# Sch_Raspi_Hat.net
KiCad netlist of a schematic drawn in Altium Designer
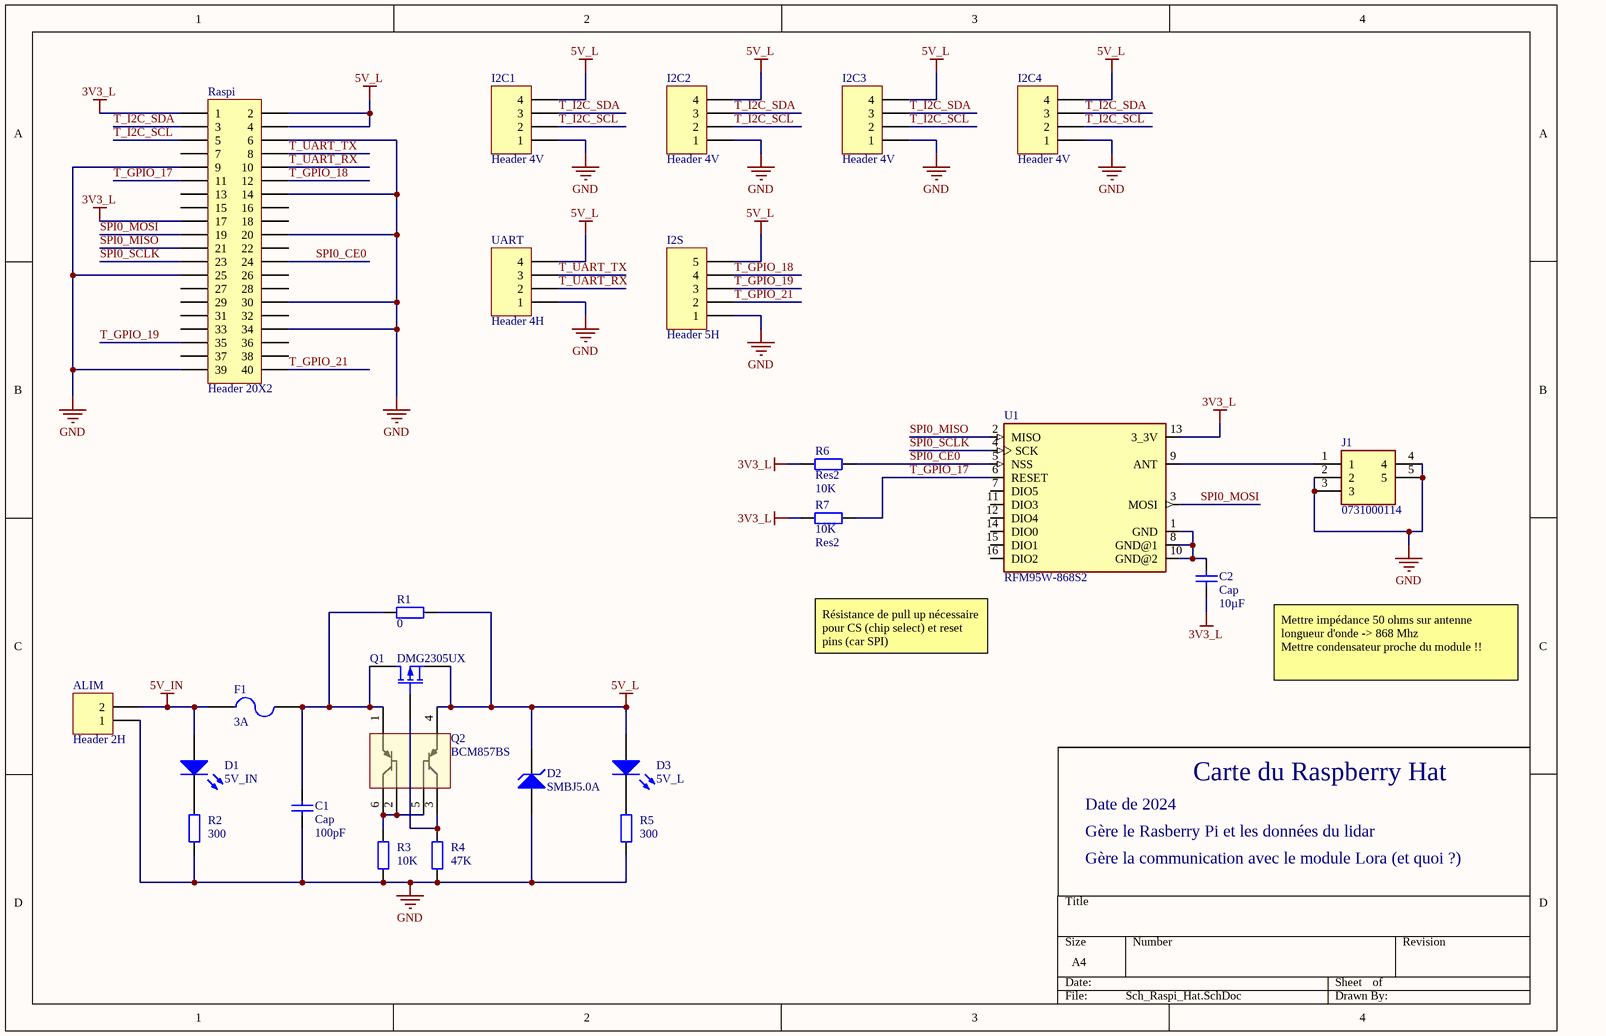
[diagram p0: Sch_Raspi_Hat.SchDoc]

(export (version "E")
  (design (tool "Eeschema 10.0.6"))
  (components
    (comp (ref "ALIM")
      (value "Header 2H")
      (footprint "Molex_MiniFitJr_2x1H")
      (description "Header, 2-Pin, Right Angle")
      (fields (field (name "PUBLISHER") "Altium Limited"))
      (libsource (lib "Miscellaneous Connectors") (part "Header 2H"))
    )
    (comp (ref "C1")
      (value "Cap")
      (footprint "Capacitor 1206")
      (description "Capacitor")
      (fields (field (name "ALTIUM_VALUE") "100pF") (field (name "PUBLISHER") "Altium Limited"))
      (libsource (lib "Miscellaneous Devices") (part "Cap"))
    )
    (comp (ref "C2")
      (value "Cap")
      (footprint "Capacitor 1206")
      (description "Capacitor")
      (fields (field (name "ALTIUM_VALUE") "10µF") (field (name "PUBLISHER") "Altium Limited"))
      (libsource (lib "Miscellaneous Devices") (part "Cap"))
    )
    (comp (ref "D1")
      (value "5V_IN")
      (footprint "KP-3216SEC")
      (description "Typical RED, GREEN, YELLOW, AMBER GaAs LED")
      (fields (field (name "PUBLISHER") "Altium Limited"))
      (libsource (lib "Miscellaneous Devices") (part "LED2"))
    )
    (comp (ref "D2")
      (value "SMBJ5.0A")
      (footprint "SMB")
      (description "Zener Diode")
      (fields (field (name "PUBLISHER") "Altium Limited"))
      (libsource (lib "Miscellaneous Devices") (part "D Zener"))
    )
    (comp (ref "D3")
      (value "5V_L")
      (footprint "KP-3216SEC")
      (description "Typical RED, GREEN, YELLOW, AMBER GaAs LED")
      (fields (field (name "PUBLISHER") "Altium Limited"))
      (libsource (lib "Miscellaneous Devices") (part "LED2"))
    )
    (comp (ref "F1")
      (value "3A")
      (footprint "Resistor 1206")
      (description "Fuse")
      (fields (field (name "PUBLISHER") "Altium Limited"))
      (libsource (lib "Miscellaneous Devices") (part "Fuse 2"))
    )
    (comp (ref "I2C1")
      (value "Header 4V")
      (footprint "B4BXHALFSN")
      (description "Header, 4-Pin, Right Angle")
      (fields (field (name "PUBLISHER") "Altium Limited"))
      (libsource (lib "Miscellaneous Connectors") (part "Header 4H"))
    )
    (comp (ref "I2C2")
      (value "Header 4V")
      (footprint "B4BXHALFSN")
      (description "Header, 4-Pin, Right Angle")
      (fields (field (name "PUBLISHER") "Altium Limited"))
      (libsource (lib "Miscellaneous Connectors") (part "Header 4H"))
    )
    (comp (ref "I2C3")
      (value "Header 4V")
      (footprint "B4BXHALFSN")
      (description "Header, 4-Pin, Right Angle")
      (fields (field (name "PUBLISHER") "Altium Limited"))
      (libsource (lib "Miscellaneous Connectors") (part "Header 4H"))
    )
    (comp (ref "I2C4")
      (value "Header 4V")
      (footprint "B4BXHALFSN")
      (description "Header, 4-Pin, Right Angle")
      (fields (field (name "PUBLISHER") "Altium Limited"))
      (libsource (lib "Miscellaneous Connectors") (part "Header 4H"))
    )
    (comp (ref "I2S")
      (value "Header 5H")
      (footprint "S5B-XH-A")
      (description "Header, 5-Pin, Right Angle")
      (fields (field (name "PUBLISHER") "Altium Limited"))
      (libsource (lib "Miscellaneous Connectors") (part "Header 5H"))
    )
    (comp (ref "J1")
      (value "0731000114")
      (footprint "0731000114")
      (description "Connector")
      (libsource (lib "*") (part "0731000114"))
    )
    (comp (ref "Q1")
      (value "DMG2305UX")
      (footprint "SOT23_L")
      (description "P-Channel MOSFET")
      (fields (field (name "PUBLISHER") "Altium Limited"))
      (libsource (lib "Miscellaneous Devices") (part "MOSFET-P"))
    )
    (comp (ref "Q2")
      (value "BCM857BS")
      (footprint "SOT65P210X110-6N")
      (description "Transistor")
      (libsource (lib "SamacSys") (part "BCM857BS"))
    )
    (comp (ref "R1")
      (value "0")
      (footprint "Resistor 1206")
      (description "Resistor")
      (fields (field (name "Comment") "Res2") (field (name "PUBLISHER") "Altium Limited"))
      (libsource (lib "") (part "Res2_2"))
    )
    (comp (ref "R2")
      (value "300")
      (footprint "Resistor 1206")
      (description "Resistor")
      (fields (field (name "Comment") "Res2") (field (name "PUBLISHER") "Altium Limited"))
      (libsource (lib "Miscellaneous Devices") (part "Res2"))
    )
    (comp (ref "R3")
      (value "10K")
      (footprint "Resistor 1206")
      (description "Resistor")
      (fields (field (name "Comment") "Res2") (field (name "PUBLISHER") "Altium Limited"))
      (libsource (lib "Miscellaneous Devices") (part "Res2"))
    )
    (comp (ref "R4")
      (value "47K")
      (footprint "Resistor 1206")
      (description "Resistor")
      (fields (field (name "Comment") "Res2") (field (name "PUBLISHER") "Altium Limited"))
      (libsource (lib "Miscellaneous Devices") (part "Res2"))
    )
    (comp (ref "R5")
      (value "300")
      (footprint "Resistor 1206")
      (description "Resistor")
      (fields (field (name "Comment") "Res2") (field (name "PUBLISHER") "Altium Limited"))
      (libsource (lib "Miscellaneous Devices") (part "Res2"))
    )
    (comp (ref "R6")
      (value "Res2")
      (footprint "Resistor 1206")
      (description "Resistor")
      (fields (field (name "ALTIUM_VALUE") "10K") (field (name "PUBLISHER") "Altium Limited"))
      (libsource (lib "") (part "Res2_1"))
    )
    (comp (ref "R7")
      (value "Res2")
      (footprint "Resistor 1206")
      (description "Resistor")
      (fields (field (name "ALTIUM_VALUE") "10K") (field (name "PUBLISHER") "Altium Limited"))
      (libsource (lib "") (part "Res2_1"))
    )
    (comp (ref "Raspi")
      (value "Header 20X2")
      (footprint "HDR2X20")
      (description "Header, 20-Pin, Dual row")
      (fields (field (name "PUBLISHER") "Altium Limited"))
      (libsource (lib "Miscellaneous Connectors") (part "Header 20X2"))
    )
    (comp (ref "U1")
      (value "RFM95W-868S2")
      (footprint "XCVR_RFM95W-868S2")
      (description "General ISM < 1GHz LoRaâ„¢ Transceiver Module 868MHz Antenna Not Included Surface Mount")
      (fields (field (name "MF") "RF"))
      (libsource (lib "LORA_RFM95W-868S2") (part "RFM95W-868S2"))
    )
    (comp (ref "UART")
      (value "Header 4H")
      (footprint "S4B-XH-A")
      (description "Header, 4-Pin, Right Angle")
      (fields (field (name "PUBLISHER") "Altium Limited"))
      (libsource (lib "Miscellaneous Connectors") (part "Header 4H"))
    )
  )
  (nets
    (net (code "1") (name "/SPI0_CE0") (class "Default")
      (node (ref "R6") (pin "2") (pinfunction "2_2") (pintype "passive"))
      (node (ref "Raspi") (pin "24") (pinfunction "24_24") (pintype "passive"))
      (node (ref "U1") (pin "5") (pinfunction "NSS_5") (pintype "input"))
    )
    (net (code "2") (name "/SPI0_MISO") (class "Default")
      (node (ref "Raspi") (pin "21") (pinfunction "21_21") (pintype "passive"))
      (node (ref "U1") (pin "2") (pinfunction "MISO_2") (pintype "input"))
    )
    (net (code "3") (name "/SPI0_MOSI") (class "Default")
      (node (ref "Raspi") (pin "19") (pinfunction "19_19") (pintype "passive"))
      (node (ref "U1") (pin "3") (pinfunction "MOSI_3") (pintype "output"))
    )
    (net (code "4") (name "/SPI0_SCLK") (class "Default")
      (node (ref "Raspi") (pin "23") (pinfunction "23_23") (pintype "passive"))
      (node (ref "U1") (pin "4") (pinfunction "SCK_4") (pintype "input"))
    )
    (net (code "5") (name "/T_GPIO_17") (class "Default")
      (node (ref "R7") (pin "2") (pinfunction "2_2") (pintype "passive"))
      (node (ref "Raspi") (pin "11") (pinfunction "11_11") (pintype "passive"))
      (node (ref "U1") (pin "6") (pinfunction "RESET_6") (pintype "bidirectional"))
    )
    (net (code "6") (name "/T_GPIO_18") (class "Default")
      (node (ref "I2S") (pin "4") (pinfunction "4_4") (pintype "passive"))
      (node (ref "Raspi") (pin "12") (pinfunction "12_12") (pintype "passive"))
    )
    (net (code "7") (name "/T_GPIO_19") (class "Default")
      (node (ref "I2S") (pin "3") (pinfunction "3_3") (pintype "passive"))
      (node (ref "Raspi") (pin "35") (pinfunction "35_35") (pintype "passive"))
    )
    (net (code "8") (name "/T_GPIO_21") (class "Default")
      (node (ref "I2S") (pin "2") (pinfunction "2_2") (pintype "passive"))
      (node (ref "Raspi") (pin "40") (pinfunction "40_40") (pintype "passive"))
    )
    (net (code "9") (name "/T_I2C_SCL") (class "Default")
      (node (ref "I2C1") (pin "2") (pinfunction "2_2") (pintype "passive"))
      (node (ref "I2C2") (pin "2") (pinfunction "2_2") (pintype "passive"))
      (node (ref "I2C3") (pin "2") (pinfunction "2_2") (pintype "passive"))
      (node (ref "I2C4") (pin "2") (pinfunction "2_2") (pintype "passive"))
      (node (ref "Raspi") (pin "5") (pinfunction "5_5") (pintype "passive"))
    )
    (net (code "10") (name "/T_I2C_SDA") (class "Default")
      (node (ref "I2C1") (pin "3") (pinfunction "3_3") (pintype "passive"))
      (node (ref "I2C2") (pin "3") (pinfunction "3_3") (pintype "passive"))
      (node (ref "I2C3") (pin "3") (pinfunction "3_3") (pintype "passive"))
      (node (ref "I2C4") (pin "3") (pinfunction "3_3") (pintype "passive"))
      (node (ref "Raspi") (pin "3") (pinfunction "3_3") (pintype "passive"))
    )
    (net (code "11") (name "/T_UART_RX") (class "Default")
      (node (ref "Raspi") (pin "10") (pinfunction "10_10") (pintype "passive"))
      (node (ref "UART") (pin "2") (pinfunction "2_2") (pintype "passive"))
    )
    (net (code "12") (name "/T_UART_TX") (class "Default")
      (node (ref "Raspi") (pin "8") (pinfunction "8_8") (pintype "passive"))
      (node (ref "UART") (pin "3") (pinfunction "3_3") (pintype "passive"))
    )
    (net (code "13") (name "3V3_L") (class "Default")
      (node (ref "C2") (pin "1") (pinfunction "1_1") (pintype "passive"))
      (node (ref "R6") (pin "1") (pinfunction "1_1") (pintype "passive"))
      (node (ref "R7") (pin "1") (pinfunction "1_1") (pintype "passive"))
      (node (ref "Raspi") (pin "1") (pinfunction "1_1") (pintype "passive"))
      (node (ref "Raspi") (pin "17") (pinfunction "17_17") (pintype "passive"))
      (node (ref "U1") (pin "13") (pinfunction "3_3V_13") (pintype "power_in"))
    )
    (net (code "14") (name "5V_IN") (class "Default")
      (node (ref "ALIM") (pin "2") (pinfunction "2_2") (pintype "passive"))
      (node (ref "D1") (pin "1") (pinfunction "A_1") (pintype "passive"))
      (node (ref "F1") (pin "1") (pinfunction "1_1") (pintype "passive"))
    )
    (net (code "15") (name "5V_L") (class "Default")
      (node (ref "D2") (pin "2") (pinfunction "K_2") (pintype "passive"))
      (node (ref "D3") (pin "1") (pinfunction "A_1") (pintype "passive"))
      (node (ref "I2C1") (pin "4") (pinfunction "4_4") (pintype "passive"))
      (node (ref "I2C2") (pin "4") (pinfunction "4_4") (pintype "passive"))
      (node (ref "I2C3") (pin "4") (pinfunction "4_4") (pintype "passive"))
      (node (ref "I2C4") (pin "4") (pinfunction "4_4") (pintype "passive"))
      (node (ref "I2S") (pin "5") (pinfunction "5_5") (pintype "passive"))
      (node (ref "Q1") (pin "3") (pinfunction "S_3") (pintype "passive"))
      (node (ref "Q2") (pin "4") (pinfunction "EMITTER_TR2_4") (pintype "passive"))
      (node (ref "R1") (pin "1") (pinfunction "1_1") (pintype "passive"))
      (node (ref "Raspi") (pin "2") (pinfunction "2_2") (pintype "passive"))
      (node (ref "Raspi") (pin "4") (pinfunction "4_4") (pintype "passive"))
      (node (ref "UART") (pin "4") (pinfunction "4_4") (pintype "passive"))
    )
    (net (code "16") (name "GND") (class "Default")
      (node (ref "ALIM") (pin "1") (pinfunction "1_1") (pintype "passive"))
      (node (ref "C1") (pin "1") (pinfunction "1_1") (pintype "passive"))
      (node (ref "D2") (pin "1") (pinfunction "A_1") (pintype "passive"))
      (node (ref "I2C1") (pin "1") (pinfunction "1_1") (pintype "passive"))
      (node (ref "I2C2") (pin "1") (pinfunction "1_1") (pintype "passive"))
      (node (ref "I2C3") (pin "1") (pinfunction "1_1") (pintype "passive"))
      (node (ref "I2C4") (pin "1") (pinfunction "1_1") (pintype "passive"))
      (node (ref "I2S") (pin "1") (pinfunction "1_1") (pintype "passive"))
      (node (ref "J1") (pin "2") (pinfunction "2_2") (pintype "passive"))
      (node (ref "J1") (pin "3") (pinfunction "3_3") (pintype "passive"))
      (node (ref "J1") (pin "4") (pinfunction "4_4") (pintype "passive"))
      (node (ref "J1") (pin "5") (pinfunction "5_5") (pintype "passive"))
      (node (ref "R2") (pin "1") (pinfunction "1_1") (pintype "passive"))
      (node (ref "R3") (pin "1") (pinfunction "1_1") (pintype "passive"))
      (node (ref "R4") (pin "1") (pinfunction "1_1") (pintype "passive"))
      (node (ref "R5") (pin "1") (pinfunction "1_1") (pintype "passive"))
      (node (ref "Raspi") (pin "14") (pinfunction "14_14") (pintype "passive"))
      (node (ref "Raspi") (pin "20") (pinfunction "20_20") (pintype "passive"))
      (node (ref "Raspi") (pin "25") (pinfunction "25_25") (pintype "passive"))
      (node (ref "Raspi") (pin "30") (pinfunction "30_30") (pintype "passive"))
      (node (ref "Raspi") (pin "34") (pinfunction "34_34") (pintype "passive"))
      (node (ref "Raspi") (pin "39") (pinfunction "39_39") (pintype "passive"))
      (node (ref "Raspi") (pin "6") (pinfunction "6_6") (pintype "passive"))
      (node (ref "Raspi") (pin "9") (pinfunction "9_9") (pintype "passive"))
      (node (ref "UART") (pin "1") (pinfunction "1_1") (pintype "passive"))
    )
    (net (code "17") (name "Net-(D1-K)") (class "Default")
      (node (ref "D1") (pin "2") (pinfunction "K_2") (pintype "passive"))
      (node (ref "R2") (pin "2") (pinfunction "2_2") (pintype "passive"))
    )
    (net (code "18") (name "Net-(D3-K)") (class "Default")
      (node (ref "D3") (pin "2") (pinfunction "K_2") (pintype "passive"))
      (node (ref "R5") (pin "2") (pinfunction "2_2") (pintype "passive"))
    )
    (net (code "19") (name "Net-(Q1-D)") (class "Default")
      (node (ref "C1") (pin "2") (pinfunction "2_2") (pintype "passive"))
      (node (ref "F1") (pin "2") (pinfunction "2_2") (pintype "passive"))
      (node (ref "Q1") (pin "1") (pinfunction "D_1") (pintype "passive"))
      (node (ref "Q2") (pin "1") (pinfunction "EMITTER_TR1_1") (pintype "passive"))
      (node (ref "R1") (pin "2") (pinfunction "2_2") (pintype "passive"))
    )
    (net (code "20") (name "Net-(Q1-G)") (class "Default")
      (node (ref "Q1") (pin "2") (pinfunction "G_2") (pintype "passive"))
      (node (ref "Q2") (pin "3") (pinfunction "COLLECTOR_TR2_3") (pintype "passive"))
      (node (ref "R4") (pin "2") (pinfunction "2_2") (pintype "passive"))
    )
    (net (code "21") (name "Net-(Q2-BASE_TR1)") (class "Default")
      (node (ref "Q2") (pin "2") (pinfunction "BASE_TR1_2") (pintype "passive"))
      (node (ref "Q2") (pin "5") (pinfunction "BASE_TR2_5") (pintype "passive"))
      (node (ref "Q2") (pin "6") (pinfunction "COLLECTOR_TR1_6") (pintype "passive"))
      (node (ref "R3") (pin "2") (pinfunction "2_2") (pintype "passive"))
    )
    (net (code "22") (name "Net-(U1-ANT)") (class "Default")
      (node (ref "J1") (pin "1") (pinfunction "1_1") (pintype "passive"))
      (node (ref "U1") (pin "9") (pinfunction "ANT_9") (pintype "passive"))
    )
    (net (code "23") (name "Net-(U1-GND)") (class "Default")
      (node (ref "C2") (pin "2") (pinfunction "2_2") (pintype "passive"))
      (node (ref "U1") (pin "1") (pinfunction "GND_1") (pintype "power_in"))
      (node (ref "U1") (pin "10") (pinfunction "GND@2_10") (pintype "power_in"))
      (node (ref "U1") (pin "8") (pinfunction "GND@1_8") (pintype "power_in"))
    )
    (net (code "24") (name "unconnected-(Raspi-Pad7)") (class "Default")
      (node (ref "Raspi") (pin "7") (pinfunction "7_7") (pintype "passive"))
    )
    (net (code "25") (name "unconnected-(Raspi-Pad13)") (class "Default")
      (node (ref "Raspi") (pin "13") (pinfunction "13_13") (pintype "passive"))
    )
    (net (code "26") (name "unconnected-(Raspi-Pad15)") (class "Default")
      (node (ref "Raspi") (pin "15") (pinfunction "15_15") (pintype "passive"))
    )
    (net (code "27") (name "unconnected-(Raspi-Pad16)") (class "Default")
      (node (ref "Raspi") (pin "16") (pinfunction "16_16") (pintype "passive"))
    )
    (net (code "28") (name "unconnected-(Raspi-Pad18)") (class "Default")
      (node (ref "Raspi") (pin "18") (pinfunction "18_18") (pintype "passive"))
    )
    (net (code "29") (name "unconnected-(Raspi-Pad22)") (class "Default")
      (node (ref "Raspi") (pin "22") (pinfunction "22_22") (pintype "passive"))
    )
    (net (code "30") (name "unconnected-(Raspi-Pad26)") (class "Default")
      (node (ref "Raspi") (pin "26") (pinfunction "26_26") (pintype "passive"))
    )
    (net (code "31") (name "unconnected-(Raspi-Pad27)") (class "Default")
      (node (ref "Raspi") (pin "27") (pinfunction "27_27") (pintype "passive"))
    )
    (net (code "32") (name "unconnected-(Raspi-Pad28)") (class "Default")
      (node (ref "Raspi") (pin "28") (pinfunction "28_28") (pintype "passive"))
    )
    (net (code "33") (name "unconnected-(Raspi-Pad29)") (class "Default")
      (node (ref "Raspi") (pin "29") (pinfunction "29_29") (pintype "passive"))
    )
    (net (code "34") (name "unconnected-(Raspi-Pad31)") (class "Default")
      (node (ref "Raspi") (pin "31") (pinfunction "31_31") (pintype "passive"))
    )
    (net (code "35") (name "unconnected-(Raspi-Pad32)") (class "Default")
      (node (ref "Raspi") (pin "32") (pinfunction "32_32") (pintype "passive"))
    )
    (net (code "36") (name "unconnected-(Raspi-Pad33)") (class "Default")
      (node (ref "Raspi") (pin "33") (pinfunction "33_33") (pintype "passive"))
    )
    (net (code "37") (name "unconnected-(Raspi-Pad36)") (class "Default")
      (node (ref "Raspi") (pin "36") (pinfunction "36_36") (pintype "passive"))
    )
    (net (code "38") (name "unconnected-(Raspi-Pad37)") (class "Default")
      (node (ref "Raspi") (pin "37") (pinfunction "37_37") (pintype "passive"))
    )
    (net (code "39") (name "unconnected-(Raspi-Pad38)") (class "Default")
      (node (ref "Raspi") (pin "38") (pinfunction "38_38") (pintype "passive"))
    )
    (net (code "40") (name "unconnected-(U1-DIO0-Pad14)") (class "Default")
      (node (ref "U1") (pin "14") (pinfunction "DIO0_14") (pintype "bidirectional"))
    )
    (net (code "41") (name "unconnected-(U1-DIO1-Pad15)") (class "Default")
      (node (ref "U1") (pin "15") (pinfunction "DIO1_15") (pintype "bidirectional"))
    )
    (net (code "42") (name "unconnected-(U1-DIO2-Pad16)") (class "Default")
      (node (ref "U1") (pin "16") (pinfunction "DIO2_16") (pintype "bidirectional"))
    )
    (net (code "43") (name "unconnected-(U1-DIO3-Pad11)") (class "Default")
      (node (ref "U1") (pin "11") (pinfunction "DIO3_11") (pintype "bidirectional"))
    )
    (net (code "44") (name "unconnected-(U1-DIO4-Pad12)") (class "Default")
      (node (ref "U1") (pin "12") (pinfunction "DIO4_12") (pintype "bidirectional"))
    )
    (net (code "45") (name "unconnected-(U1-DIO5-Pad7)") (class "Default")
      (node (ref "U1") (pin "7") (pinfunction "DIO5_7") (pintype "bidirectional"))
    )
  )
)
